# Amplifier_Module_D1.net
KiCad netlist of a schematic drawn in EasyEDA Pro
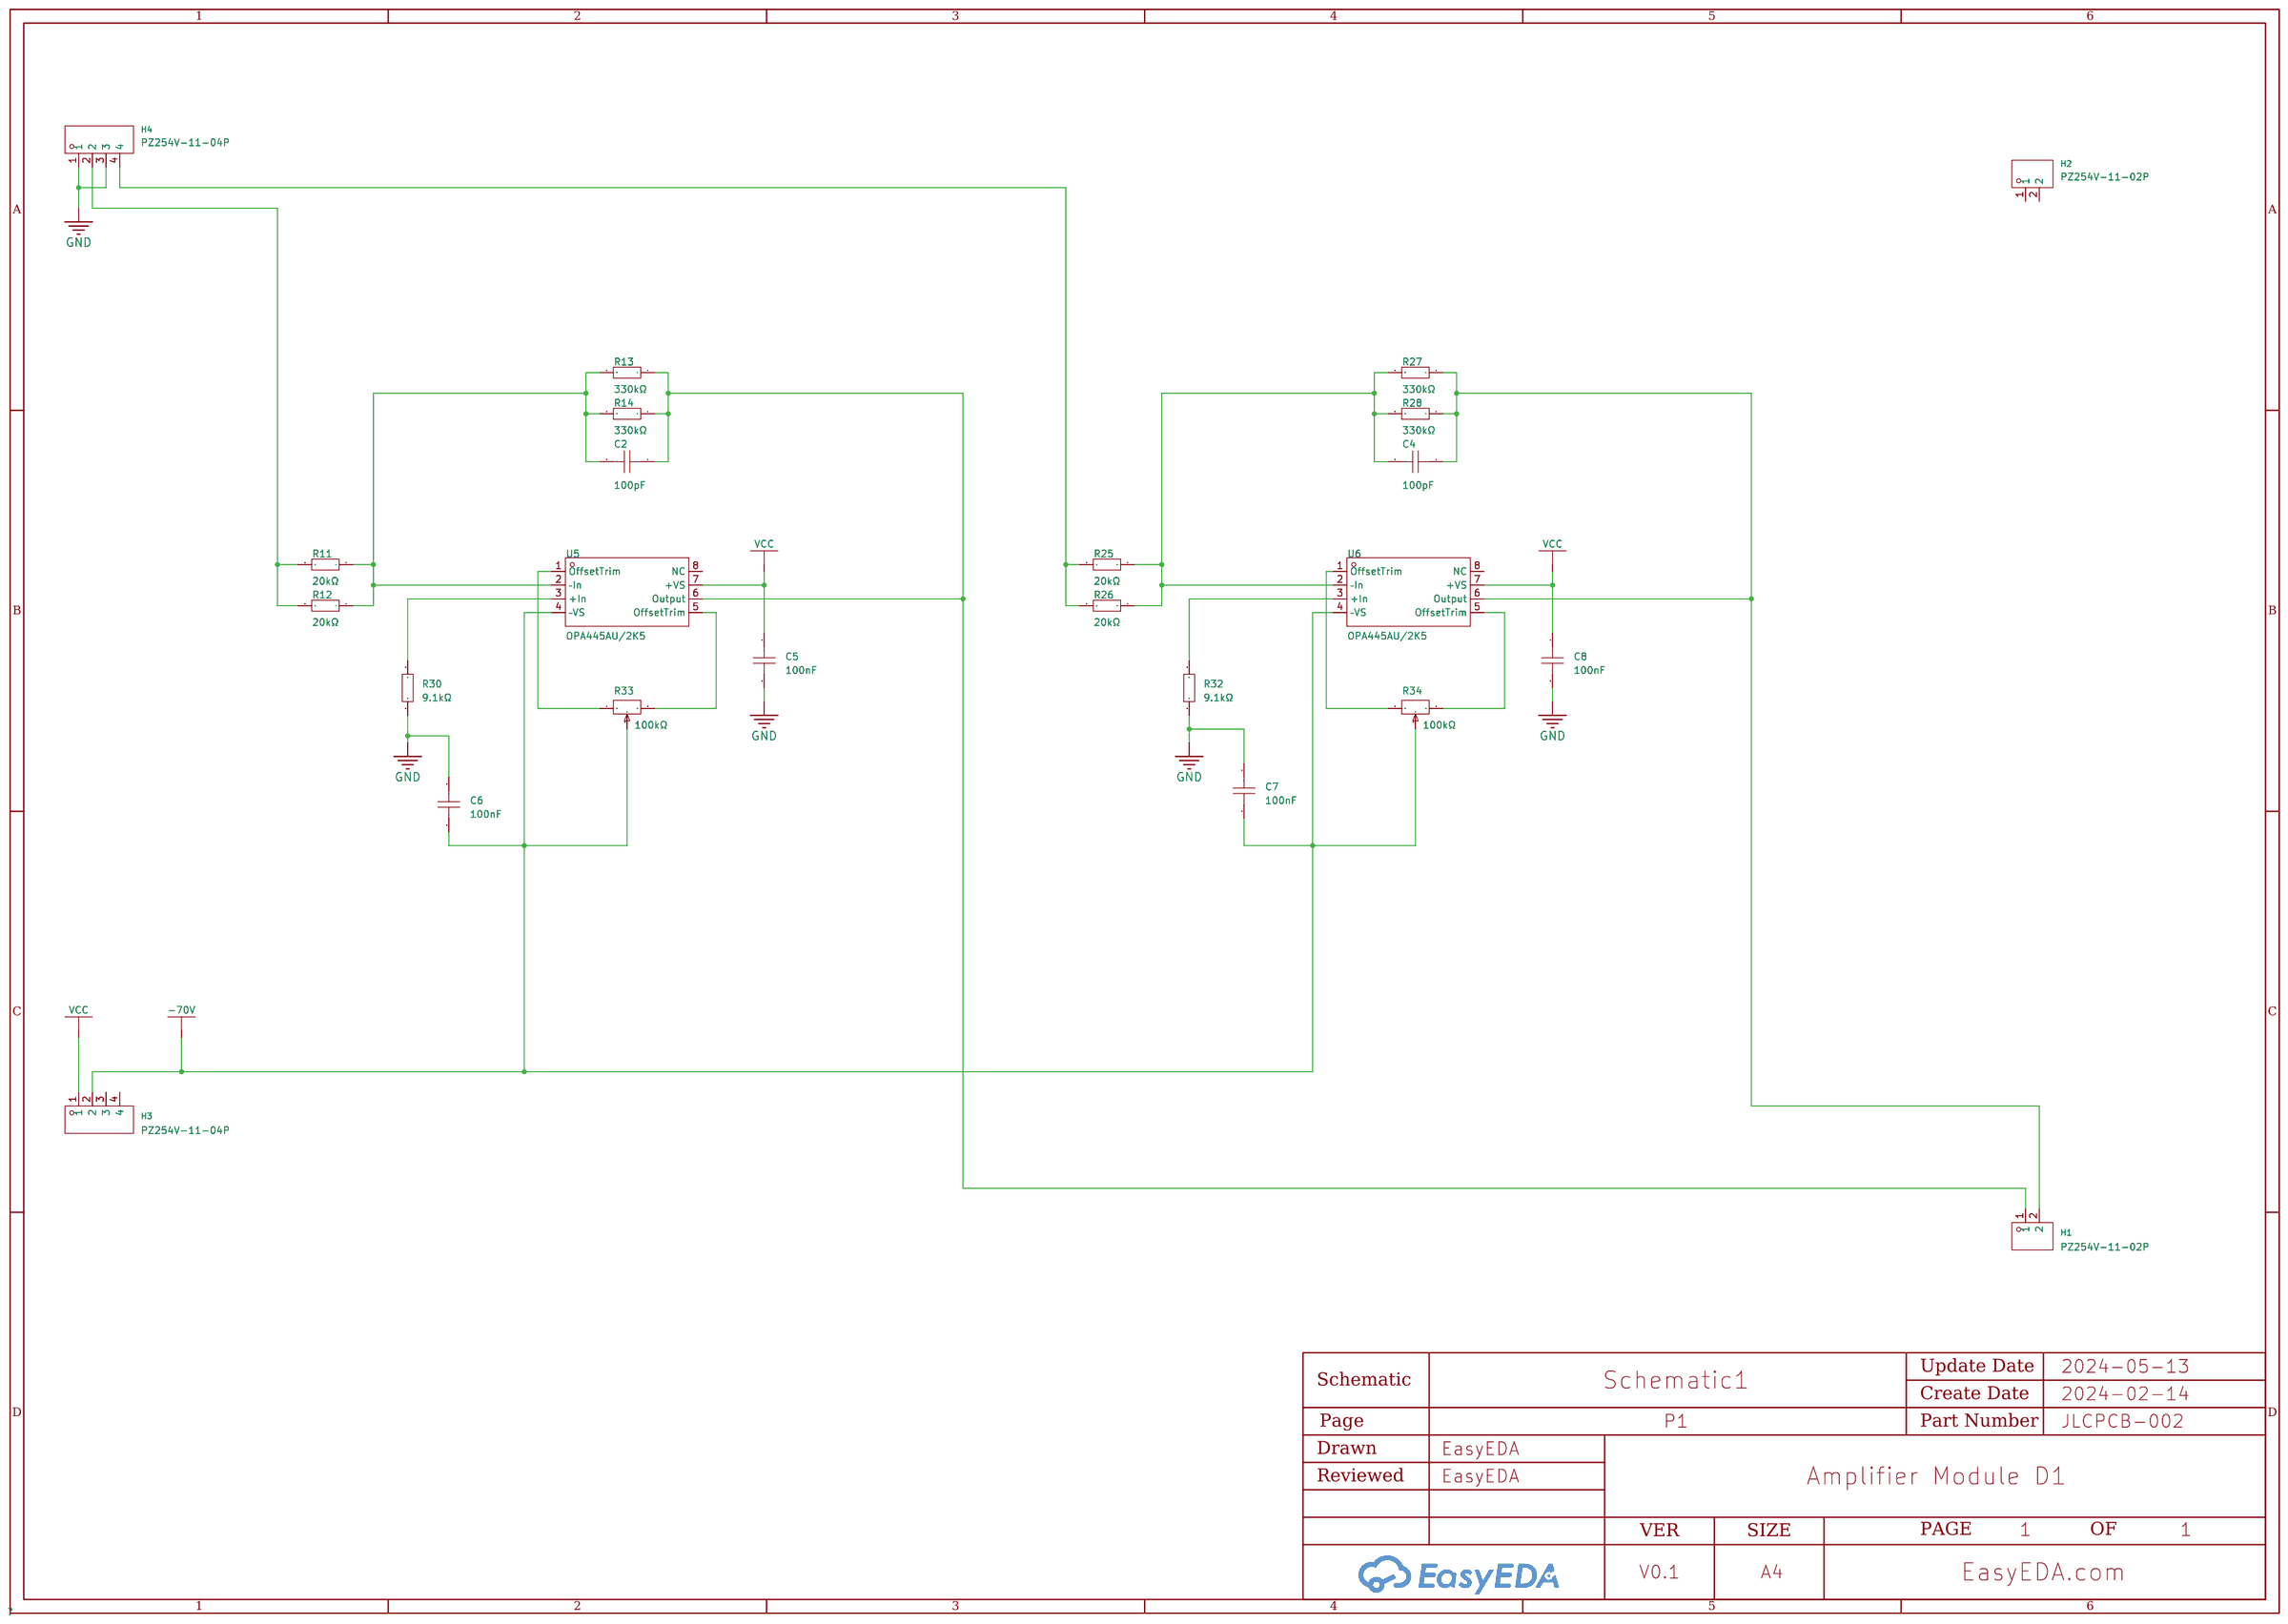
[diagram p0: schematic sheet]

(export (version "E")
  (design (tool "Eeschema 10.0.6"))
  (components
    (comp (ref "C2")
      (value "100pF")
      (footprint "easyedapro:C0603")
      (fields (field (name "Manufacturer Part") "0603CG101J101NT") (field (name "Manufacturer") "FH(风华)"))
      (libsource (lib "easyedapro") (part "CAP"))
    )
    (comp (ref "C4")
      (value "100pF")
      (footprint "easyedapro:C0603")
      (fields (field (name "Manufacturer Part") "0603CG101J101NT") (field (name "Manufacturer") "FH(风华)"))
      (libsource (lib "easyedapro") (part "CAP"))
    )
    (comp (ref "C5")
      (value "100nF")
      (footprint "easyedapro:C0603")
      (fields (field (name "Manufacturer Part") "0603B104K101NT") (field (name "Manufacturer") "FH(风华)"))
      (libsource (lib "easyedapro") (part "CAP"))
    )
    (comp (ref "C6")
      (value "100nF")
      (footprint "easyedapro:C0603")
      (fields (field (name "Manufacturer Part") "0603B104K101NT") (field (name "Manufacturer") "FH(风华)"))
      (libsource (lib "easyedapro") (part "CAP"))
    )
    (comp (ref "C7")
      (value "100nF")
      (footprint "easyedapro:C0603")
      (fields (field (name "Manufacturer Part") "0603B104K101NT") (field (name "Manufacturer") "FH(风华)"))
      (libsource (lib "easyedapro") (part "CAP"))
    )
    (comp (ref "C8")
      (value "100nF")
      (footprint "easyedapro:C0603")
      (fields (field (name "Manufacturer Part") "0603B104K101NT") (field (name "Manufacturer") "FH(风华)"))
      (libsource (lib "easyedapro") (part "CAP"))
    )
    (comp (ref "H1")
      (value "PZ254V-11-02P")
      (footprint "easyedapro:HDR-TH_2P-P2.54-V-M")
      (fields (field (name "Manufacturer") "XFCN(兴飞)"))
      (libsource (lib "easyedapro") (part "PZ254V-11-02P"))
    )
    (comp (ref "H2")
      (value "PZ254V-11-02P")
      (footprint "easyedapro:HDR-TH_2P-P2.54-V-M")
      (fields (field (name "Manufacturer") "XFCN(兴飞)"))
      (libsource (lib "easyedapro") (part "PZ254V-11-02P"))
    )
    (comp (ref "H3")
      (value "PZ254V-11-04P")
      (footprint "easyedapro:HDR-TH_4P-P2.54-V-M")
      (fields (field (name "Manufacturer") "XFCN(兴飞)"))
      (libsource (lib "easyedapro") (part "PZ254V-11-04P_C2691448"))
    )
    (comp (ref "H4")
      (value "PZ254V-11-04P")
      (footprint "easyedapro:HDR-TH_4P-P2.54-V-M")
      (fields (field (name "Manufacturer") "XFCN(兴飞)"))
      (libsource (lib "easyedapro") (part "PZ254V-11-04P_C2691448"))
    )
    (comp (ref "R11")
      (value "20kΩ")
      (footprint "easyedapro:R0603")
      (fields
        (field (name "Manufacturer Part") "0603WAF2002T5E")
        (field (name "Manufacturer") "UNI-ROYAL(厚声)")
      )
      (libsource (lib "easyedapro") (part "Res"))
    )
    (comp (ref "R12")
      (value "20kΩ")
      (footprint "easyedapro:R0603")
      (fields
        (field (name "Manufacturer Part") "0603WAF2002T5E")
        (field (name "Manufacturer") "UNI-ROYAL(厚声)")
      )
      (libsource (lib "easyedapro") (part "Res"))
    )
    (comp (ref "R13")
      (value "330kΩ")
      (footprint "easyedapro:R0603")
      (fields
        (field (name "Manufacturer Part") "0603WAF3303T5E")
        (field (name "Manufacturer") "UNI-ROYAL(厚声)")
      )
      (libsource (lib "easyedapro") (part "Res"))
    )
    (comp (ref "R14")
      (value "330kΩ")
      (footprint "easyedapro:R0603")
      (fields
        (field (name "Manufacturer Part") "0603WAF3303T5E")
        (field (name "Manufacturer") "UNI-ROYAL(厚声)")
      )
      (libsource (lib "easyedapro") (part "Res"))
    )
    (comp (ref "R25")
      (value "20kΩ")
      (footprint "easyedapro:R0603")
      (fields
        (field (name "Manufacturer Part") "0603WAF2002T5E")
        (field (name "Manufacturer") "UNI-ROYAL(厚声)")
      )
      (libsource (lib "easyedapro") (part "Res"))
    )
    (comp (ref "R26")
      (value "20kΩ")
      (footprint "easyedapro:R0603")
      (fields
        (field (name "Manufacturer Part") "0603WAF2002T5E")
        (field (name "Manufacturer") "UNI-ROYAL(厚声)")
      )
      (libsource (lib "easyedapro") (part "Res"))
    )
    (comp (ref "R27")
      (value "330kΩ")
      (footprint "easyedapro:R0603")
      (fields
        (field (name "Manufacturer Part") "0603WAF3303T5E")
        (field (name "Manufacturer") "UNI-ROYAL(厚声)")
      )
      (libsource (lib "easyedapro") (part "Res"))
    )
    (comp (ref "R28")
      (value "330kΩ")
      (footprint "easyedapro:R0603")
      (fields
        (field (name "Manufacturer Part") "0603WAF3303T5E")
        (field (name "Manufacturer") "UNI-ROYAL(厚声)")
      )
      (libsource (lib "easyedapro") (part "Res"))
    )
    (comp (ref "R30")
      (value "9.1kΩ")
      (footprint "easyedapro:R0603")
      (fields
        (field (name "Manufacturer Part") "0603WAF9101T5E")
        (field (name "Manufacturer") "UNI-ROYAL(厚声)")
      )
      (libsource (lib "easyedapro") (part "Res"))
    )
    (comp (ref "R32")
      (value "9.1kΩ")
      (footprint "easyedapro:R0603")
      (fields
        (field (name "Manufacturer Part") "0603WAF9101T5E")
        (field (name "Manufacturer") "UNI-ROYAL(厚声)")
      )
      (libsource (lib "easyedapro") (part "Res"))
    )
    (comp (ref "R33")
      (value "100kΩ")
      (footprint "easyedapro:RES-ADJ-TH_3296W")
      (fields (field (name "Manufacturer Part") "3296W-1-104LF") (field (name "Manufacturer") "BOURNS"))
      (libsource (lib "easyedapro") (part "3296W-1-104LF"))
    )
    (comp (ref "R34")
      (value "100kΩ")
      (footprint "easyedapro:RES-ADJ-TH_3296W")
      (fields (field (name "Manufacturer Part") "3296W-1-104LF") (field (name "Manufacturer") "BOURNS"))
      (libsource (lib "easyedapro") (part "3296W-1-104LF"))
    )
    (comp (ref "U5")
      (value "OPA445AU/2K5")
      (footprint "easyedapro:SOIC-8_L4.9-W3.9-P1.27-LS6.0-BL")
      (fields (field (name "Manufacturer") "TI(德州仪器)"))
      (libsource (lib "easyedapro") (part "OPA445AU/2K5"))
    )
    (comp (ref "U6")
      (value "OPA445AU/2K5")
      (footprint "easyedapro:SOIC-8_L4.9-W3.9-P1.27-LS6.0-BL")
      (fields (field (name "Manufacturer") "TI(德州仪器)"))
      (libsource (lib "easyedapro") (part "OPA445AU/2K5"))
    )
  )
  (nets
    (net (code "1") (name "-70V") (class "Default")
      (node (ref "C6") (pin "2") (pinfunction "2_2") (pintype "input"))
      (node (ref "C7") (pin "2") (pinfunction "2_2") (pintype "input"))
      (node (ref "H3") (pin "2") (pinfunction "2_2") (pintype "input"))
      (node (ref "R33") (pin "2") (pinfunction "2_2") (pintype "input"))
      (node (ref "R34") (pin "2") (pinfunction "2_2") (pintype "input"))
      (node (ref "U5") (pin "4") (pinfunction "–VS_4") (pintype "unspecified"))
      (node (ref "U6") (pin "4") (pinfunction "–VS_4") (pintype "unspecified"))
    )
    (net (code "2") (name "GND") (class "Default")
      (node (ref "C5") (pin "2") (pinfunction "2_2") (pintype "input"))
      (node (ref "C6") (pin "1") (pinfunction "1_1") (pintype "input"))
      (node (ref "C7") (pin "1") (pinfunction "1_1") (pintype "input"))
      (node (ref "C8") (pin "2") (pinfunction "2_2") (pintype "input"))
      (node (ref "H4") (pin "1") (pinfunction "1_1") (pintype "input"))
      (node (ref "H4") (pin "3") (pinfunction "3_3") (pintype "input"))
      (node (ref "R30") (pin "1") (pinfunction "1_1") (pintype "input"))
      (node (ref "R32") (pin "1") (pinfunction "1_1") (pintype "input"))
    )
    (net (code "3") (name "Net-(H4-Pad2)") (class "Default")
      (node (ref "H4") (pin "2") (pinfunction "2_2") (pintype "input"))
      (node (ref "R11") (pin "2") (pinfunction "2_2") (pintype "input"))
      (node (ref "R12") (pin "2") (pinfunction "2_2") (pintype "input"))
    )
    (net (code "4") (name "Net-(H4-Pad4)") (class "Default")
      (node (ref "H4") (pin "4") (pinfunction "4_4") (pintype "input"))
      (node (ref "R25") (pin "2") (pinfunction "2_2") (pintype "input"))
      (node (ref "R26") (pin "2") (pinfunction "2_2") (pintype "input"))
    )
    (net (code "5") (name "Net-(R33-Pad1)") (class "Default")
      (node (ref "R33") (pin "1") (pinfunction "1_1") (pintype "input"))
      (node (ref "U5") (pin "1") (pinfunction "OffsetTrim_1") (pintype "unspecified"))
    )
    (net (code "6") (name "Net-(R33-Pad3)") (class "Default")
      (node (ref "R33") (pin "3") (pinfunction "3_3") (pintype "input"))
      (node (ref "U5") (pin "5") (pinfunction "OffsetTrim_5") (pintype "unspecified"))
    )
    (net (code "7") (name "Net-(R34-Pad1)") (class "Default")
      (node (ref "R34") (pin "1") (pinfunction "1_1") (pintype "input"))
      (node (ref "U6") (pin "1") (pinfunction "OffsetTrim_1") (pintype "unspecified"))
    )
    (net (code "8") (name "Net-(R34-Pad3)") (class "Default")
      (node (ref "R34") (pin "3") (pinfunction "3_3") (pintype "input"))
      (node (ref "U6") (pin "5") (pinfunction "OffsetTrim_5") (pintype "unspecified"))
    )
    (net (code "9") (name "Net-(U5-+In)") (class "Default")
      (node (ref "R30") (pin "2") (pinfunction "2_2") (pintype "input"))
      (node (ref "U5") (pin "3") (pinfunction "+In_3") (pintype "unspecified"))
    )
    (net (code "10") (name "Net-(U5-Output)") (class "Default")
      (node (ref "C2") (pin "1") (pinfunction "1_1") (pintype "input"))
      (node (ref "H1") (pin "1") (pinfunction "1_1") (pintype "input"))
      (node (ref "R13") (pin "1") (pinfunction "1_1") (pintype "input"))
      (node (ref "R14") (pin "1") (pinfunction "1_1") (pintype "input"))
      (node (ref "U5") (pin "6") (pinfunction "Output_6") (pintype "unspecified"))
    )
    (net (code "11") (name "Net-(U5-–In)") (class "Default")
      (node (ref "C2") (pin "2") (pinfunction "2_2") (pintype "input"))
      (node (ref "R11") (pin "1") (pinfunction "1_1") (pintype "input"))
      (node (ref "R12") (pin "1") (pinfunction "1_1") (pintype "input"))
      (node (ref "R13") (pin "2") (pinfunction "2_2") (pintype "input"))
      (node (ref "R14") (pin "2") (pinfunction "2_2") (pintype "input"))
      (node (ref "U5") (pin "2") (pinfunction "–In_2") (pintype "unspecified"))
    )
    (net (code "12") (name "Net-(U6-+In)") (class "Default")
      (node (ref "R32") (pin "2") (pinfunction "2_2") (pintype "input"))
      (node (ref "U6") (pin "3") (pinfunction "+In_3") (pintype "unspecified"))
    )
    (net (code "13") (name "Net-(U6-Output)") (class "Default")
      (node (ref "C4") (pin "1") (pinfunction "1_1") (pintype "input"))
      (node (ref "H1") (pin "2") (pinfunction "2_2") (pintype "input"))
      (node (ref "R27") (pin "1") (pinfunction "1_1") (pintype "input"))
      (node (ref "R28") (pin "1") (pinfunction "1_1") (pintype "input"))
      (node (ref "U6") (pin "6") (pinfunction "Output_6") (pintype "unspecified"))
    )
    (net (code "14") (name "Net-(U6-–In)") (class "Default")
      (node (ref "C4") (pin "2") (pinfunction "2_2") (pintype "input"))
      (node (ref "R25") (pin "1") (pinfunction "1_1") (pintype "input"))
      (node (ref "R26") (pin "1") (pinfunction "1_1") (pintype "input"))
      (node (ref "R27") (pin "2") (pinfunction "2_2") (pintype "input"))
      (node (ref "R28") (pin "2") (pinfunction "2_2") (pintype "input"))
      (node (ref "U6") (pin "2") (pinfunction "–In_2") (pintype "unspecified"))
    )
    (net (code "15") (name "VCC") (class "Default")
      (node (ref "C5") (pin "1") (pinfunction "1_1") (pintype "input"))
      (node (ref "C8") (pin "1") (pinfunction "1_1") (pintype "input"))
      (node (ref "H3") (pin "1") (pinfunction "1_1") (pintype "input"))
      (node (ref "U5") (pin "7") (pinfunction "+VS_7") (pintype "unspecified"))
      (node (ref "U6") (pin "7") (pinfunction "+VS_7") (pintype "unspecified"))
    )
    (net (code "16") (name "unconnected-(H2-Pad1)") (class "Default")
      (node (ref "H2") (pin "1") (pinfunction "1_1") (pintype "input"))
    )
    (net (code "17") (name "unconnected-(H2-Pad2)") (class "Default")
      (node (ref "H2") (pin "2") (pinfunction "2_2") (pintype "input"))
    )
    (net (code "18") (name "unconnected-(H3-Pad3)") (class "Default")
      (node (ref "H3") (pin "3") (pinfunction "3_3") (pintype "input"))
    )
    (net (code "19") (name "unconnected-(H3-Pad4)") (class "Default")
      (node (ref "H3") (pin "4") (pinfunction "4_4") (pintype "input"))
    )
    (net (code "20") (name "unconnected-(U5-NC-Pad8)") (class "Default")
      (node (ref "U5") (pin "8") (pinfunction "NC_8") (pintype "unspecified"))
    )
    (net (code "21") (name "unconnected-(U6-NC-Pad8)") (class "Default")
      (node (ref "U6") (pin "8") (pinfunction "NC_8") (pintype "unspecified"))
    )
  )
)
